# Nuio_LeftKeyboard_Rev_E_3_Power.net
KiCad netlist of a schematic drawn in Altium Designer
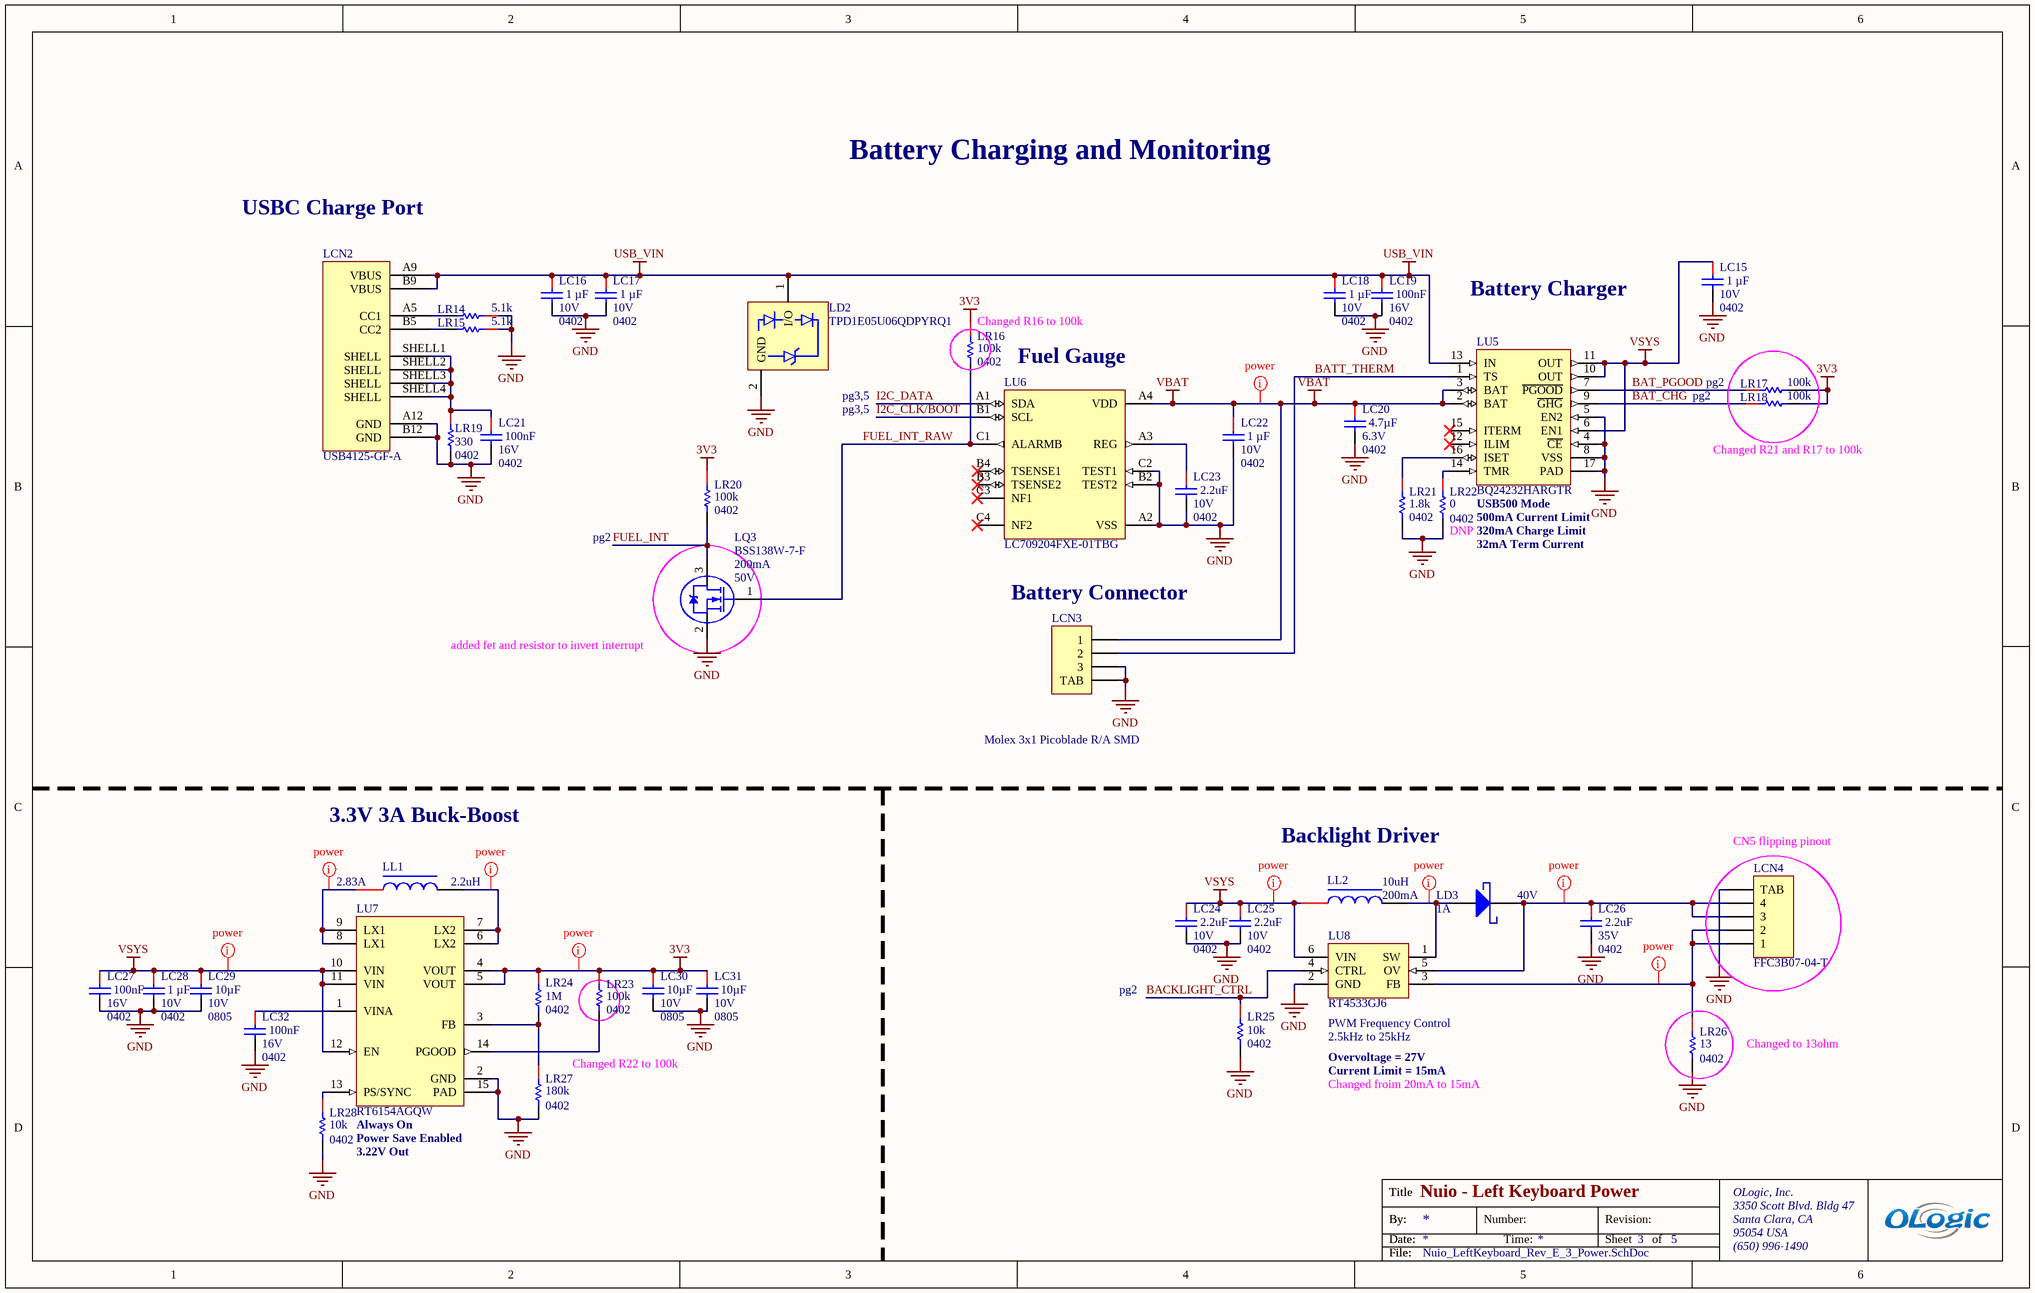
[diagram p0: Nuio_LeftKeyboard_Rev_E_3_Power.SchDoc]

(export (version "E")
  (design (tool "Eeschema 10.0.6"))
  (components
    (comp (ref "LC15")
      (value "CAP CER 1UF 10V X5R 0402")
      (footprint "CAPC0402(1005)_L")
      (description "±20% 10V Ceramic Capacitor X5R 0402 (1005 Metric)")
      (fields
        (field (name "PACKAGE (IMPERIAL)") "0402")
        (field (name "VOLTAGE (RATED)") "10V")
        (field (name "CAPACITANCE") "1 µF")
        (field (name "MANUFACTURER PART NUMBER") "CC0402MRX5R6BB105")
        (field (name "TOLERANCE") "±20%")
      )
      (libsource (lib "OLogic Nexus Vault") (part "OL_Capacitor"))
    )
    (comp (ref "LC16")
      (value "CAP CER 1UF 10V X5R 0402")
      (footprint "CAPC0402(1005)_L")
      (description "±20% 10V Ceramic Capacitor X5R 0402 (1005 Metric)")
      (fields
        (field (name "PACKAGE (IMPERIAL)") "0402")
        (field (name "VOLTAGE (RATED)") "10V")
        (field (name "CAPACITANCE") "1 µF")
        (field (name "MANUFACTURER PART NUMBER") "CC0402MRX5R6BB105")
        (field (name "TOLERANCE") "±20%")
      )
      (libsource (lib "OLogic Nexus Vault") (part "OL_Capacitor"))
    )
    (comp (ref "LC17")
      (value "CAP CER 1UF 10V X5R 0402")
      (footprint "CAPC0402(1005)_L")
      (description "±20% 10V Ceramic Capacitor X5R 0402 (1005 Metric)")
      (fields
        (field (name "PACKAGE (IMPERIAL)") "0402")
        (field (name "VOLTAGE (RATED)") "10V")
        (field (name "CAPACITANCE") "1 µF")
        (field (name "MANUFACTURER PART NUMBER") "CC0402MRX5R6BB105")
        (field (name "TOLERANCE") "±20%")
      )
      (libsource (lib "OLogic Nexus Vault") (part "OL_Capacitor"))
    )
    (comp (ref "LC18")
      (value "CAP CER 1UF 10V X5R 0402")
      (footprint "CAPC0402(1005)_L")
      (description "±20% 10V Ceramic Capacitor X5R 0402 (1005 Metric)")
      (fields
        (field (name "PACKAGE (IMPERIAL)") "0402")
        (field (name "VOLTAGE (RATED)") "10V")
        (field (name "CAPACITANCE") "1 µF")
        (field (name "MANUFACTURER PART NUMBER") "CC0402MRX5R6BB105")
        (field (name "TOLERANCE") "±20%")
      )
      (libsource (lib "OLogic Nexus Vault") (part "OL_Capacitor"))
    )
    (comp (ref "LC19")
      (value "CAP CER 0.1UF 16V X5R 0402")
      (footprint "CAPC0402(1005)_L")
      (description "±10% 16V Ceramic Capacitor X5R 0402 (1005 Metric)")
      (fields
        (field (name "PACKAGE (IMPERIAL)") "0402")
        (field (name "VOLTAGE (RATED)") "16V")
        (field (name "CAPACITANCE") "100nF")
        (field (name "MANUFACTURER") "Taiyo Yuden")
        (field (name "MANUFACTURER PART NUMBER") "EMK105BJ104KV-F")
      )
      (libsource (lib "OLogic Nexus Vault") (part "OL_Capacitor"))
    )
    (comp (ref "LC20")
      (value "4.7uF")
      (footprint "CAPC0402(1005)_L")
      (description "CAP CER 4.7UF 6.3V 10% X5R 0402")
      (fields
        (field (name "PACKAGE (IMPERIAL)") "0402")
        (field (name "VOLTAGE (RATED)") "6.3V")
        (field (name "CAPACITANCE") "4.7µF")
        (field (name "TOLERANCE") "20%")
      )
      (libsource (lib "OLogic Nexus Vault") (part "OL_Capacitor"))
    )
    (comp (ref "LC21")
      (value "CAP CER 0.1UF 16V X5R 0402")
      (footprint "CAPC0402(1005)_L")
      (description "±10% 16V Ceramic Capacitor X5R 0402 (1005 Metric)")
      (fields
        (field (name "PACKAGE (IMPERIAL)") "0402")
        (field (name "VOLTAGE (RATED)") "16V")
        (field (name "CAPACITANCE") "100nF")
        (field (name "MANUFACTURER") "Taiyo Yuden")
        (field (name "MANUFACTURER PART NUMBER") "EMK105BJ104KV-F")
      )
      (libsource (lib "OLogic Nexus Vault") (part "OL_Capacitor"))
    )
    (comp (ref "LC22")
      (value "CAP CER 1UF 10V X5R 0402")
      (footprint "CAPC0402(1005)_L")
      (description "±20% 10V Ceramic Capacitor X5R 0402 (1005 Metric)")
      (fields
        (field (name "PACKAGE (IMPERIAL)") "0402")
        (field (name "VOLTAGE (RATED)") "10V")
        (field (name "CAPACITANCE") "1 µF")
        (field (name "MANUFACTURER PART NUMBER") "CC0402MRX5R6BB105")
        (field (name "TOLERANCE") "±20%")
      )
      (libsource (lib "OLogic Nexus Vault") (part "OL_Capacitor"))
    )
    (comp (ref "LC23")
      (value "CAP CER 2.2UF 10V X5R 0402")
      (footprint "CAPC0402(1005)_L")
      (description "±20% 10V Ceramic Capacitor X5R 0402 (1005 Metric)")
      (fields
        (field (name "PACKAGE (IMPERIAL)") "0402")
        (field (name "VOLTAGE (RATED)") "10V")
        (field (name "CAPACITANCE") "2.2uF")
        (field (name "TOLERANCE") "20%")
        (field (name "MANUFACTURER") "KEMET")
      )
      (libsource (lib "OLogic Nexus Vault") (part "OL_Capacitor"))
    )
    (comp (ref "LC24")
      (value "CAP CER 2.2UF 10V X5R 0402")
      (footprint "CAPC0402(1005)_L")
      (description "±20% 10V Ceramic Capacitor X5R 0402 (1005 Metric)")
      (fields
        (field (name "PACKAGE (IMPERIAL)") "0402")
        (field (name "VOLTAGE (RATED)") "10V")
        (field (name "CAPACITANCE") "2.2uF")
        (field (name "TOLERANCE") "20%")
        (field (name "MANUFACTURER") "KEMET")
      )
      (libsource (lib "OLogic Nexus Vault") (part "OL_Capacitor"))
    )
    (comp (ref "LC25")
      (value "CAP CER 2.2UF 10V X5R 0402")
      (footprint "CAPC0402(1005)_L")
      (description "±20% 10V Ceramic Capacitor X5R 0402 (1005 Metric)")
      (fields
        (field (name "PACKAGE (IMPERIAL)") "0402")
        (field (name "VOLTAGE (RATED)") "10V")
        (field (name "CAPACITANCE") "2.2uF")
        (field (name "TOLERANCE") "20%")
        (field (name "MANUFACTURER") "KEMET")
      )
      (libsource (lib "OLogic Nexus Vault") (part "OL_Capacitor"))
    )
    (comp (ref "LC26")
      (value "2.2uF")
      (footprint "CAPC0402(1005)_L")
      (description "CAP CER 2.2UF 35V 10% X5R 0402")
      (fields
        (field (name "VOLTAGE (RATED)") "35V")
        (field (name "PACKAGE (IMPERIAL)") "0402")
        (field (name "TOLERANCE") "10%")
      )
      (libsource (lib "OLogic Nexus Vault") (part "=Capacitance"))
    )
    (comp (ref "LC27")
      (value "CAP CER 0.1UF 16V X5R 0402")
      (footprint "CAPC0402(1005)_L")
      (description "±10% 16V Ceramic Capacitor X5R 0402 (1005 Metric)")
      (fields
        (field (name "PACKAGE (IMPERIAL)") "0402")
        (field (name "VOLTAGE (RATED)") "16V")
        (field (name "CAPACITANCE") "100nF")
        (field (name "MANUFACTURER") "Taiyo Yuden")
        (field (name "MANUFACTURER PART NUMBER") "EMK105BJ104KV-F")
      )
      (libsource (lib "OLogic Nexus Vault") (part "OL_Capacitor"))
    )
    (comp (ref "LC28")
      (value "CAP CER 1UF 10V X5R 0402")
      (footprint "CAPC0402(1005)_L")
      (description "±20% 10V Ceramic Capacitor X5R 0402 (1005 Metric)")
      (fields
        (field (name "PACKAGE (IMPERIAL)") "0402")
        (field (name "VOLTAGE (RATED)") "10V")
        (field (name "CAPACITANCE") "1 µF")
        (field (name "MANUFACTURER PART NUMBER") "CC0402MRX5R6BB105")
        (field (name "TOLERANCE") "±20%")
      )
      (libsource (lib "OLogic Nexus Vault") (part "OL_Capacitor"))
    )
    (comp (ref "LC29")
      (value "CAP CER 10UF 10V X7R 0805")
      (footprint "CAPC0805(2012)_L")
      (description "10µF ±10% 10V Ceramic Capacitor X7R 0805 (2012 Metric)")
      (fields
        (field (name "VOLTAGE (RATED)") "10V")
        (field (name "PACKAGE (IMPERIAL)") "0805")
        (field (name "CAPACITANCE") "10µF")
        (field (name "TOLERANCE") "10%")
        (field (name "MANUFACTURER PART NUMBER") "GRM21BR71A106KA73K")
      )
      (libsource (lib "OLogic Nexus Vault") (part "OL_Capacitor"))
    )
    (comp (ref "LC30")
      (value "CAP CER 10UF 10V X7R 0805")
      (footprint "CAPC0805(2012)_L")
      (description "10µF ±10% 10V Ceramic Capacitor X7R 0805 (2012 Metric)")
      (fields
        (field (name "VOLTAGE (RATED)") "10V")
        (field (name "PACKAGE (IMPERIAL)") "0805")
        (field (name "CAPACITANCE") "10µF")
        (field (name "TOLERANCE") "10%")
        (field (name "MANUFACTURER PART NUMBER") "GRM21BR71A106KA73K")
      )
      (libsource (lib "OLogic Nexus Vault") (part "OL_Capacitor"))
    )
    (comp (ref "LC31")
      (value "CAP CER 10UF 10V X7R 0805")
      (footprint "CAPC0805(2012)_L")
      (description "10µF ±10% 10V Ceramic Capacitor X7R 0805 (2012 Metric)")
      (fields
        (field (name "VOLTAGE (RATED)") "10V")
        (field (name "PACKAGE (IMPERIAL)") "0805")
        (field (name "CAPACITANCE") "10µF")
        (field (name "TOLERANCE") "10%")
        (field (name "MANUFACTURER PART NUMBER") "GRM21BR71A106KA73K")
      )
      (libsource (lib "OLogic Nexus Vault") (part "OL_Capacitor"))
    )
    (comp (ref "LC32")
      (value "CAP CER 0.1UF 16V X5R 0402")
      (footprint "CAPC0402(1005)_L")
      (description "±10% 16V Ceramic Capacitor X5R 0402 (1005 Metric)")
      (fields
        (field (name "PACKAGE (IMPERIAL)") "0402")
        (field (name "VOLTAGE (RATED)") "16V")
        (field (name "CAPACITANCE") "100nF")
        (field (name "MANUFACTURER") "Taiyo Yuden")
        (field (name "MANUFACTURER PART NUMBER") "EMK105BJ104KV-F")
      )
      (libsource (lib "OLogic Nexus Vault") (part "OL_Capacitor"))
    )
    (comp (ref "LCN2")
      (value "USB4125-GF-A")
      (footprint "USB4125-GF-A")
      (fields (field (name "MANUFACTURER") "GCT") (field (name "VOLTAGE") "20V"))
      (libsource (lib "OLogic Nexus Vault") (part "USB4125-GF-A"))
    )
    (comp (ref "LCN3")
      (value "Molex 3x1 Picoblade R/A SMD")
      (footprint "Molex 3x1 Picoblade R_A SMD")
      (fields (field (name "MANUFACTURER PART NUMBER") "0532610371") (field (name "MANUFACTURER") "Molex"))
      (libsource (lib "OLogic Nexus Vault") (part "Molex 3x1 Picoblade R/A SMD"))
    )
    (comp (ref "LCN4")
      (value "FFC3B07-04-T")
      (footprint "FFC3B07-04-T")
      (fields (field (name "MANUFACTURER") "GCT"))
      (libsource (lib "OLogic Nexus Vault") (part "FFC3B07-04-T"))
    )
    (comp (ref "LD2")
      (value "TPD1E05U06QDPYRQ1")
      (footprint "FP-DPY0002A-MFG")
      (description "TVS DIODE 5.5V 14V 2X1SON")
      (fields (field (name "MANUFACTURER") "Texas Instruments"))
      (libsource (lib "OLogic Nexus Vault") (part "TPD1E05U06QDPYRQ1"))
    )
    (comp (ref "LD3")
      (value "PMEG4010AESBYL")
      (footprint "PMEG4010AESBYL-Footprint-1")
      (description "DIODE SCHOTTKY 40V 1A SOD993")
      (fields (field (name "DC REVERSE VOLTAGE MAX") "40V") (field (name "CURRENT AVG RECTIFIED") "1A"))
      (libsource (lib "OLogic Nexus Vault") (part "PMEG4010AESB"))
    )
    (comp (ref "LL1")
      (value "FIXED IND 2.2UH 2.83A 74MOHM SMD")
      (footprint "FIXED IND 2.2UH 2.83A 74MOHM SMD")
      (description "2.2 µH Shielded Wirewound Inductor 2.83 A 74mOhm Max Nonstandard -")
      (fields
        (field (name "INDUCTANCE") "2.2uH")
        (field (name "CURRENT RATING (AMPS)") "2.83A")
        (field (name "MANUFACTURER") "TDK Corporation")
      )
      (libsource (lib "OLogic Nexus Vault") (part "OL_Inductor"))
    )
    (comp (ref "LL2")
      (value "10uH")
      (footprint "FIXED IND 10UH 300MA 680MOHM SMD")
      (description "10 µH Shielded Multilayer Inductor 300 mA 680mOhm 0805 (2012 Metric)")
      (fields
        (field (name "MANUFACTURER PART NUMBER") "MLZ2012M100HT000")
        (field (name "TOLERANCE") "20%")
        (field (name "SATURATION CURRENT") "200mA")
      )
      (libsource (lib "OLogic Nexus Vault") (part "OL_Inductor"))
    )
    (comp (ref "LQ3")
      (value "BSS138W-7-F")
      (footprint "DIOD-SOT323-3_V")
      (description "DIODES INC. - BSS138W-7-F. - BSS FAMILY SOT323 T&R 3K ROHS COMPLIANT: YES")
      (fields
        (field (name "VOLTAGE") "50V")
        (field (name "POWER") "200mW")
        (field (name "CONTINUOUS DRAIN CURRENT (ID)") "200mA")
        (field (name "VOLTAGE RATING (DC)") "50V")
      )
      (libsource (lib "OLogic Nexus Vault") (part "OL_NFET_GSD"))
    )
    (comp (ref "LR14")
      (value "RES SMD 5.1K OHM 1% 1/10W 0402")
      (footprint "RESC0402(1005)_L")
      (description "5.1 kOhms ±1% 0.1W, 1/10W Chip Resistor 0402 (1005 Metric) Automotive AEC-Q200 Thick Film")
      (fields
        (field (name "RESISTANCE") "5.1k")
        (field (name "POWER") "63mW")
        (field (name "TOLERANCE") "1%")
      )
      (libsource (lib "OLogic Nexus Vault") (part "=Resistance"))
    )
    (comp (ref "LR15")
      (value "RES SMD 5.1K OHM 1% 1/10W 0402")
      (footprint "RESC0402(1005)_L")
      (description "5.1 kOhms ±1% 0.1W, 1/10W Chip Resistor 0402 (1005 Metric) Automotive AEC-Q200 Thick Film")
      (fields
        (field (name "RESISTANCE") "5.1k")
        (field (name "POWER") "63mW")
        (field (name "TOLERANCE") "1%")
      )
      (libsource (lib "OLogic Nexus Vault") (part "=Resistance"))
    )
    (comp (ref "LR16")
      (value "100k")
      (footprint "RESC0402(1005)_L")
      (description "±1% 0.063W, 1/16W Chip Resistor 0402 (1005 Metric) Moisture Resistant Thick Film")
      (fields
        (field (name "CASE CODE (IMPERIAL)") "0402")
        (field (name "TOLERANCE") "1%")
        (field (name "MANUFACTURER") "YAGEO")
      )
      (libsource (lib "OLogic Nexus Vault") (part "=Resistance"))
    )
    (comp (ref "LR17")
      (value "100k")
      (footprint "RESC0402(1005)_L")
      (description "±1% 0.063W, 1/16W Chip Resistor 0402 (1005 Metric) Moisture Resistant Thick Film")
      (fields (field (name "TOLERANCE") "1%") (field (name "MANUFACTURER") "YAGEO"))
      (libsource (lib "OLogic Nexus Vault") (part "=Resistance"))
    )
    (comp (ref "LR18")
      (value "100k")
      (footprint "RESC0402(1005)_L")
      (description "±1% 0.063W, 1/16W Chip Resistor 0402 (1005 Metric) Moisture Resistant Thick Film")
      (fields (field (name "TOLERANCE") "1%") (field (name "MANUFACTURER") "YAGEO"))
      (libsource (lib "OLogic Nexus Vault") (part "=Resistance"))
    )
    (comp (ref "LR19")
      (value "RES SMD 330 OHM 1% 1/16W 0402")
      (footprint "RESC0402(1005)_L")
      (description "330 Ohms ±1% 0.063W, 1/16W Chip Resistor 0402 (1005 Metric) Automotive AEC-Q200 Thick Film")
      (fields
        (field (name "RESISTANCE") "330")
        (field (name "PACKAGE (IMPERIAL)") "0402")
        (field (name "POWER") "63mW")
        (field (name "TOLERANCE") "1%")
      )
      (libsource (lib "OLogic Nexus Vault") (part "OL_Resistor"))
    )
    (comp (ref "LR20")
      (value "100k")
      (footprint "RESC0402(1005)_L")
      (description "±1% 0.063W, 1/16W Chip Resistor 0402 (1005 Metric) Moisture Resistant Thick Film")
      (fields
        (field (name "CASE CODE (IMPERIAL)") "0402")
        (field (name "TOLERANCE") "1%")
        (field (name "MANUFACTURER") "YAGEO")
      )
      (libsource (lib "OLogic Nexus Vault") (part "=Resistance"))
    )
    (comp (ref "LR21")
      (value "1.8k")
      (footprint "RESC0402(1005)_L")
      (description "1.8 kOhms ±0.1% 0.063W, 1/16W Chip Resistor 0402 (1005 Metric) Automotive AEC-Q200 Thin Film")
      (fields
        (field (name "TOLERANCE") "0.1%")
        (field (name "CASE CODE (IMPERIAL)") "0402")
        (field (name "MANUFACTURER") "Panasonic Electronic Components")
      )
      (libsource (lib "OLogic Nexus Vault") (part "=Resistance"))
    )
    (comp (ref "LR22")
      (value "RES 0 OHM JUMPER 1/16W 0402")
      (footprint "RESC0402(1005)_L")
      (description "0 Ohms Jumper Chip Resistor 0402 (1005 Metric) Automotive AEC-Q200 Thick Film")
      (fields
        (field (name "PACKAGE (IMPERIAL)") "0402")
        (field (name "RESISTANCE") "0")
        (field (name "POWER") "63mW")
        (field (name "TOLERANCE") "0%")
      )
      (libsource (lib "OLogic Nexus Vault") (part "=Resistance"))
    )
    (comp (ref "LR23")
      (value "100k")
      (footprint "RESC0402(1005)_L")
      (description "±1% 0.063W, 1/16W Chip Resistor 0402 (1005 Metric) Moisture Resistant Thick Film")
      (fields
        (field (name "CASE CODE (IMPERIAL)") "0402")
        (field (name "TOLERANCE") "1%")
        (field (name "MANUFACTURER") "YAGEO")
      )
      (libsource (lib "OLogic Nexus Vault") (part "=Resistance"))
    )
    (comp (ref "LR24")
      (value "RES 1M OHM 1% 1/16W 0402")
      (footprint "RESC0402(1005)_L")
      (description "1 MOhms ±1% 0.063W, 1/16W Chip Resistor 0402 (1005 Metric) Moisture Resistant Thick Film")
      (fields
        (field (name "RESISTANCE") "1M")
        (field (name "CASE/PACKAGE") "0402")
        (field (name "MANUFACTURER") "YAGEO")
        (field (name "MANUFACTURER PART NUMBER") "RC0402FR-071ML")
      )
      (libsource (lib "OLogic Nexus Vault") (part "OL_Resistor"))
    )
    (comp (ref "LR25")
      (value "RES SMD 10K OHM 1% 1/16W 0402")
      (footprint "RESC0402_YAGEO")
      (fields
        (field (name "RESISTANCE") "10k")
        (field (name "PACKAGE (IMPERIAL)") "0402")
        (field (name "MANUFACTURER") "Yageo")
        (field (name "TOLERANCE") "1%")
        (field (name "MANUFACTURER PART NUMBER") "AT0402FRE0710KL")
      )
      (libsource (lib "OLogic Nexus Vault") (part "OL_Resistor"))
    )
    (comp (ref "LR26")
      (value "13")
      (footprint "RESC0402(1005)_L")
      (description "RES 13 OHM 1% 1/16W 0402")
      (fields
        (field (name "PACKAGE (IMPERIAL)") "0402")
        (field (name "POWER") "63mW")
        (field (name "TOLERANCE") "1%")
        (field (name "RESISTANCE") "13")
      )
      (libsource (lib "OLogic Nexus Vault") (part "=Resistance"))
    )
    (comp (ref "LR27")
      (value "180k")
      (footprint "RESC0402(1005)_L")
      (description "RES 180K OHM 1% 1/16W 0402")
      (fields
        (field (name "PACKAGE (IMPERIAL)") "0402")
        (field (name "POWER") "63mW")
        (field (name "TOLERANCE") "1%")
        (field (name "RESISTANCE") "180k")
      )
      (libsource (lib "OLogic Nexus Vault") (part "=Resistance"))
    )
    (comp (ref "LR28")
      (value "RES SMD 10K OHM 1% 1/16W 0402")
      (footprint "RESC0402(1005)_L")
      (description "10 kOhms ±1% 0.063W, 1/16W Chip Resistor 0402 (1005 Metric) Thin Film")
      (fields
        (field (name "PACKAGE (IMPERIAL)") "0402")
        (field (name "RESISTANCE") "10k")
        (field (name "POWER") "63mW")
        (field (name "TOLERANCE") "1%")
      )
      (libsource (lib "OLogic Nexus Vault") (part "=Resistance"))
    )
    (comp (ref "LU5")
      (value "BQ24232HARGTR")
      (footprint "BQ24232HARGTR")
      (description "USB Friendly 0.5A Li-ion charger with power-Path, 10.5V OVP 16-VQFN -5 to 125")
      (fields (field (name "MANUFACTURER") "Texas Instruments"))
      (libsource (lib "OLogic Nexus Vault") (part "BQ24232HARGTR"))
    )
    (comp (ref "LU6")
      (value "LC709204FXE-01TBG")
      (footprint "BGA12C40P4X3_191X148X51")
      (description "IC FUEL GAUGE LI-ION 1C 12WLCSP")
      (fields (field (name "MANUFACTURER") "onsemi"))
      (libsource (lib "OLogic Nexus Vault") (part "LC709204FXE-01TBG"))
    )
    (comp (ref "LU7")
      (value "RT6154AGQW")
      (footprint "PSON50P300X80_HS-15N")
      (description "IC REG BCK BST ADJ 4A 14WDFN")
      (fields (field (name "MANUFACTURER") "Richtek USA Inc."))
      (libsource (lib "OLogic Nexus Vault") (part "RT6154AGQW"))
    )
    (comp (ref "LU8")
      (value "RT4533GJ6")
      (footprint "RT4533GJ6")
      (description "IC LED DRVR RGLTR PWM TSOT23-6")
      (libsource (lib "OLogic Nexus Vault") (part "RT4533GJ6"))
    )
  )
  (nets
    (net (code "1") (name "/BACKLIGHT_CTRL") (class "Default")
      (node (ref "LR25") (pin "1") (pinfunction "1_1") (pintype "passive"))
      (node (ref "LU8") (pin "4") (pinfunction "CTRL_4") (pintype "input"))
    )
    (net (code "2") (name "/BATT_THERM") (class "Default")
      (node (ref "LCN3") (pin "2") (pinfunction "2_2") (pintype "passive"))
      (node (ref "LU5") (pin "1") (pinfunction "TS_1") (pintype "input"))
    )
    (net (code "3") (name "/BAT_CHG") (class "Default")
      (node (ref "LR18") (pin "1") (pinfunction "1_1") (pintype "passive"))
      (node (ref "LU5") (pin "9") (pinfunction "~{GHG}_9") (pintype "output"))
    )
    (net (code "4") (name "/BAT_PGOOD") (class "Default")
      (node (ref "LR17") (pin "1") (pinfunction "1_1") (pintype "passive"))
      (node (ref "LU5") (pin "7") (pinfunction "~{PGOOD}_7") (pintype "output"))
    )
    (net (code "5") (name "/FUEL_INT") (class "Default")
      (node (ref "LQ3") (pin "3") (pinfunction "D_3") (pintype "passive"))
      (node (ref "LR20") (pin "2") (pinfunction "2_2") (pintype "passive"))
    )
    (net (code "6") (name "/FUEL_INT_RAW") (class "Default")
      (node (ref "LQ3") (pin "1") (pinfunction "G_1") (pintype "passive"))
      (node (ref "LR16") (pin "2") (pinfunction "2_2") (pintype "passive"))
      (node (ref "LU6") (pin "C1") (pinfunction "ALARMB_C1") (pintype "output"))
    )
    (net (code "7") (name "/I2C_CLK{slash}BOOT") (class "Default")
      (node (ref "LU6") (pin "B1") (pinfunction "SCL_B1") (pintype "bidirectional"))
    )
    (net (code "8") (name "/I2C_DATA") (class "Default")
      (node (ref "LU6") (pin "A1") (pinfunction "SDA_A1") (pintype "bidirectional"))
    )
    (net (code "9") (name "3V3") (class "Default")
      (node (ref "LC30") (pin "1") (pinfunction "1_1") (pintype "passive"))
      (node (ref "LC31") (pin "1") (pinfunction "1_1") (pintype "passive"))
      (node (ref "LR16") (pin "1") (pinfunction "1_1") (pintype "passive"))
      (node (ref "LR17") (pin "2") (pinfunction "2_2") (pintype "passive"))
      (node (ref "LR18") (pin "2") (pinfunction "2_2") (pintype "passive"))
      (node (ref "LR20") (pin "1") (pinfunction "1_1") (pintype "passive"))
      (node (ref "LR23") (pin "1") (pinfunction "1_1") (pintype "passive"))
      (node (ref "LR24") (pin "1") (pinfunction "1_1") (pintype "passive"))
      (node (ref "LU7") (pin "4") (pinfunction "VOUT_4") (pintype "power_in"))
      (node (ref "LU7") (pin "5") (pinfunction "VOUT_5") (pintype "power_in"))
    )
    (net (code "10") (name "GND") (class "Default")
      (node (ref "LC15") (pin "2") (pinfunction "2_2") (pintype "passive"))
      (node (ref "LC16") (pin "2") (pinfunction "2_2") (pintype "passive"))
      (node (ref "LC17") (pin "2") (pinfunction "2_2") (pintype "passive"))
      (node (ref "LC18") (pin "2") (pinfunction "2_2") (pintype "passive"))
      (node (ref "LC19") (pin "2") (pinfunction "2_2") (pintype "passive"))
      (node (ref "LC20") (pin "2") (pinfunction "2_2") (pintype "passive"))
      (node (ref "LC21") (pin "2") (pinfunction "2_2") (pintype "passive"))
      (node (ref "LC22") (pin "2") (pinfunction "2_2") (pintype "passive"))
      (node (ref "LC23") (pin "2") (pinfunction "2_2") (pintype "passive"))
      (node (ref "LC24") (pin "2") (pinfunction "2_2") (pintype "passive"))
      (node (ref "LC25") (pin "2") (pinfunction "2_2") (pintype "passive"))
      (node (ref "LC26") (pin "2") (pinfunction "2_2") (pintype "passive"))
      (node (ref "LC27") (pin "2") (pinfunction "2_2") (pintype "passive"))
      (node (ref "LC28") (pin "2") (pinfunction "2_2") (pintype "passive"))
      (node (ref "LC29") (pin "2") (pinfunction "2_2") (pintype "passive"))
      (node (ref "LC30") (pin "2") (pinfunction "2_2") (pintype "passive"))
      (node (ref "LC31") (pin "2") (pinfunction "2_2") (pintype "passive"))
      (node (ref "LC32") (pin "2") (pinfunction "2_2") (pintype "passive"))
      (node (ref "LCN2") (pin "A12") (pinfunction "GND_A12") (pintype "passive"))
      (node (ref "LCN2") (pin "B12") (pinfunction "GND_B12") (pintype "passive"))
      (node (ref "LCN3") (pin "0") (pinfunction "TAB_0") (pintype "passive"))
      (node (ref "LCN3") (pin "3") (pinfunction "3_3") (pintype "passive"))
      (node (ref "LCN4") (pin "0") (pinfunction "TAB_0") (pintype "passive"))
      (node (ref "LD2") (pin "2") (pinfunction "GND_2") (pintype "passive"))
      (node (ref "LQ3") (pin "2") (pinfunction "S_2") (pintype "passive"))
      (node (ref "LR14") (pin "1") (pinfunction "1_1") (pintype "passive"))
      (node (ref "LR15") (pin "1") (pinfunction "1_1") (pintype "passive"))
      (node (ref "LR19") (pin "2") (pinfunction "2_2") (pintype "passive"))
      (node (ref "LR21") (pin "2") (pinfunction "2_2") (pintype "passive"))
      (node (ref "LR22") (pin "2") (pinfunction "2_2") (pintype "passive"))
      (node (ref "LR25") (pin "2") (pinfunction "2_2") (pintype "passive"))
      (node (ref "LR26") (pin "2") (pinfunction "2_2") (pintype "passive"))
      (node (ref "LR27") (pin "2") (pinfunction "2_2") (pintype "passive"))
      (node (ref "LR28") (pin "2") (pinfunction "2_2") (pintype "passive"))
      (node (ref "LU5") (pin "17") (pinfunction "PAD_17") (pintype "passive"))
      (node (ref "LU5") (pin "4") (pinfunction "~{CE}_4") (pintype "input"))
      (node (ref "LU5") (pin "5") (pinfunction "EN2_5") (pintype "input"))
      (node (ref "LU5") (pin "8") (pinfunction "VSS_8") (pintype "power_in"))
      (node (ref "LU6") (pin "A2") (pinfunction "VSS_A2") (pintype "power_in"))
      (node (ref "LU6") (pin "B2") (pinfunction "TEST2_B2") (pintype "input"))
      (node (ref "LU6") (pin "C2") (pinfunction "TEST1_C2") (pintype "input"))
      (node (ref "LU7") (pin "15") (pinfunction "PAD_15") (pintype "power_in"))
      (node (ref "LU7") (pin "2") (pinfunction "GND_2") (pintype "power_in"))
      (node (ref "LU8") (pin "2") (pinfunction "GND_2") (pintype "power_in"))
    )
    (net (code "11") (name "Net-(LC21-Pad1)") (class "Default")
      (node (ref "LC21") (pin "1") (pinfunction "1_1") (pintype "passive"))
      (node (ref "LCN2") (pin "SHELL1") (pinfunction "SHELL_SHELL1") (pintype "passive"))
      (node (ref "LCN2") (pin "SHELL2") (pinfunction "SHELL_SHELL2") (pintype "passive"))
      (node (ref "LCN2") (pin "SHELL3") (pinfunction "SHELL_SHELL3") (pintype "passive"))
      (node (ref "LCN2") (pin "SHELL4") (pinfunction "SHELL_SHELL4") (pintype "passive"))
      (node (ref "LR19") (pin "1") (pinfunction "1_1") (pintype "passive"))
    )
    (net (code "12") (name "Net-(LCN2-CC1)") (class "Default")
      (node (ref "LCN2") (pin "A5") (pinfunction "CC1_A5") (pintype "passive"))
      (node (ref "LR14") (pin "2") (pinfunction "2_2") (pintype "passive"))
    )
    (net (code "13") (name "Net-(LCN2-CC2)") (class "Default")
      (node (ref "LCN2") (pin "B5") (pinfunction "CC2_B5") (pintype "passive"))
      (node (ref "LR15") (pin "2") (pinfunction "2_2") (pintype "passive"))
    )
    (net (code "14") (name "Net-(LD3-A)") (class "Default")
      (node (ref "LD3") (pin "2") (pinfunction "A_2") (pintype "passive"))
      (node (ref "LL2") (pin "2") (pinfunction "2_2") (pintype "passive"))
      (node (ref "LU8") (pin "1") (pinfunction "SW_1") (pintype "passive"))
    )
    (net (code "15") (name "Net-(LD3-K)") (class "Default")
      (node (ref "LC26") (pin "1") (pinfunction "1_1") (pintype "passive"))
      (node (ref "LCN4") (pin "3") (pinfunction "3_3") (pintype "passive"))
      (node (ref "LCN4") (pin "4") (pinfunction "4_4") (pintype "passive"))
      (node (ref "LD3") (pin "1") (pinfunction "K_1") (pintype "passive"))
      (node (ref "LU8") (pin "5") (pinfunction "OV_5") (pintype "input"))
    )
    (net (code "16") (name "Net-(LL1-Pad1)") (class "Default")
      (node (ref "LL1") (pin "1") (pinfunction "1_1") (pintype "passive"))
      (node (ref "LU7") (pin "8") (pinfunction "LX1_8") (pintype "passive"))
      (node (ref "LU7") (pin "9") (pinfunction "LX1_9") (pintype "passive"))
    )
    (net (code "17") (name "Net-(LL1-Pad2)") (class "Default")
      (node (ref "LL1") (pin "2") (pinfunction "2_2") (pintype "passive"))
      (node (ref "LU7") (pin "6") (pinfunction "LX2_6") (pintype "passive"))
      (node (ref "LU7") (pin "7") (pinfunction "LX2_7") (pintype "passive"))
    )
    (net (code "18") (name "Net-(LU5-ISET)") (class "Default")
      (node (ref "LR21") (pin "1") (pinfunction "1_1") (pintype "passive"))
      (node (ref "LU5") (pin "16") (pinfunction "ISET_16") (pintype "bidirectional"))
    )
    (net (code "19") (name "Net-(LU5-TMR)") (class "Default")
      (node (ref "LR22") (pin "1") (pinfunction "1_1") (pintype "passive"))
      (node (ref "LU5") (pin "14") (pinfunction "TMR_14") (pintype "input"))
    )
    (net (code "20") (name "Net-(LU6-REG)") (class "Default")
      (node (ref "LC23") (pin "1") (pinfunction "1_1") (pintype "passive"))
      (node (ref "LU6") (pin "A3") (pinfunction "REG_A3") (pintype "output"))
    )
    (net (code "21") (name "Net-(LU7-FB)") (class "Default")
      (node (ref "LR24") (pin "2") (pinfunction "2_2") (pintype "passive"))
      (node (ref "LR27") (pin "1") (pinfunction "1_1") (pintype "passive"))
      (node (ref "LU7") (pin "3") (pinfunction "FB_3") (pintype "passive"))
    )
    (net (code "22") (name "Net-(LU7-PGOOD)") (class "Default")
      (node (ref "LR23") (pin "2") (pinfunction "2_2") (pintype "passive"))
      (node (ref "LU7") (pin "14") (pinfunction "PGOOD_14") (pintype "output"))
    )
    (net (code "23") (name "Net-(LU7-PS{slash}SYNC)") (class "Default")
      (node (ref "LR28") (pin "1") (pinfunction "1_1") (pintype "passive"))
      (node (ref "LU7") (pin "13") (pinfunction "PS/SYNC_13") (pintype "input"))
    )
    (net (code "24") (name "Net-(LU7-VINA)") (class "Default")
      (node (ref "LC32") (pin "1") (pinfunction "1_1") (pintype "passive"))
      (node (ref "LU7") (pin "1") (pinfunction "VINA_1") (pintype "power_in"))
    )
    (net (code "25") (name "Net-(LU8-FB)") (class "Default")
      (node (ref "LCN4") (pin "1") (pinfunction "1_1") (pintype "passive"))
      (node (ref "LCN4") (pin "2") (pinfunction "2_2") (pintype "passive"))
      (node (ref "LR26") (pin "1") (pinfunction "1_1") (pintype "passive"))
      (node (ref "LU8") (pin "3") (pinfunction "FB_3") (pintype "passive"))
    )
    (net (code "26") (name "USB_VIN") (class "Default")
      (node (ref "LC16") (pin "1") (pinfunction "1_1") (pintype "passive"))
      (node (ref "LC17") (pin "1") (pinfunction "1_1") (pintype "passive"))
      (node (ref "LC18") (pin "1") (pinfunction "1_1") (pintype "passive"))
      (node (ref "LC19") (pin "1") (pinfunction "1_1") (pintype "passive"))
      (node (ref "LCN2") (pin "A9") (pinfunction "VBUS_A9") (pintype "passive"))
      (node (ref "LCN2") (pin "B9") (pinfunction "VBUS_B9") (pintype "passive"))
      (node (ref "LD2") (pin "1") (pinfunction "I/O_1") (pintype "passive"))
      (node (ref "LU5") (pin "13") (pinfunction "IN_13") (pintype "input"))
    )
    (net (code "27") (name "VBAT") (class "Default")
      (node (ref "LC20") (pin "1") (pinfunction "1_1") (pintype "passive"))
      (node (ref "LC22") (pin "1") (pinfunction "1_1") (pintype "passive"))
      (node (ref "LCN3") (pin "1") (pinfunction "1_1") (pintype "passive"))
      (node (ref "LU5") (pin "2") (pinfunction "BAT_2") (pintype "bidirectional"))
      (node (ref "LU5") (pin "3") (pinfunction "BAT_3") (pintype "bidirectional"))
      (node (ref "LU6") (pin "A4") (pinfunction "VDD_A4") (pintype "power_in"))
    )
    (net (code "28") (name "VSYS") (class "Default")
      (node (ref "LC15") (pin "1") (pinfunction "1_1") (pintype "passive"))
      (node (ref "LC24") (pin "1") (pinfunction "1_1") (pintype "passive"))
      (node (ref "LC25") (pin "1") (pinfunction "1_1") (pintype "passive"))
      (node (ref "LC27") (pin "1") (pinfunction "1_1") (pintype "passive"))
      (node (ref "LC28") (pin "1") (pinfunction "1_1") (pintype "passive"))
      (node (ref "LC29") (pin "1") (pinfunction "1_1") (pintype "passive"))
      (node (ref "LL2") (pin "1") (pinfunction "1_1") (pintype "passive"))
      (node (ref "LU5") (pin "10") (pinfunction "OUT_10") (pintype "output"))
      (node (ref "LU5") (pin "11") (pinfunction "OUT_11") (pintype "output"))
      (node (ref "LU5") (pin "6") (pinfunction "EN1_6") (pintype "input"))
      (node (ref "LU7") (pin "10") (pinfunction "VIN_10") (pintype "power_in"))
      (node (ref "LU7") (pin "11") (pinfunction "VIN_11") (pintype "power_in"))
      (node (ref "LU7") (pin "12") (pinfunction "EN_12") (pintype "input"))
      (node (ref "LU8") (pin "6") (pinfunction "VIN_6") (pintype "power_in"))
    )
    (net (code "29") (name "unconnected-(LU5-ILIM-Pad12)") (class "Default")
      (node (ref "LU5") (pin "12") (pinfunction "ILIM_12") (pintype "input+no_connect"))
    )
    (net (code "30") (name "unconnected-(LU5-ITERM-Pad15)") (class "Default")
      (node (ref "LU5") (pin "15") (pinfunction "ITERM_15") (pintype "input+no_connect"))
    )
    (net (code "31") (name "unconnected-(LU6-NF1-PadC3)") (class "Default")
      (node (ref "LU6") (pin "C3") (pinfunction "NF1_C3") (pintype "passive+no_connect"))
    )
    (net (code "32") (name "unconnected-(LU6-NF2-PadC4)") (class "Default")
      (node (ref "LU6") (pin "C4") (pinfunction "NF2_C4") (pintype "passive+no_connect"))
    )
    (net (code "33") (name "unconnected-(LU6-TSENSE1-PadB4)") (class "Default")
      (node (ref "LU6") (pin "B4") (pinfunction "TSENSE1_B4") (pintype "bidirectional+no_connect"))
    )
    (net (code "34") (name "unconnected-(LU6-TSENSE2-PadB3)") (class "Default")
      (node (ref "LU6") (pin "B3") (pinfunction "TSENSE2_B3") (pintype "bidirectional+no_connect"))
    )
  )
)
